# Front_PowerConnectors.net
KiCad netlist of a schematic drawn in Altium Designer
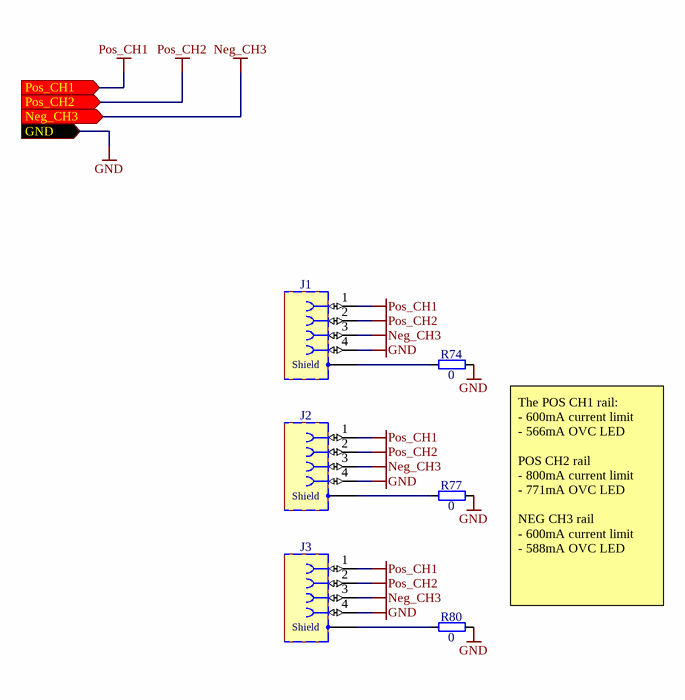
[diagram p0: Front_PowerConnectors.SchDoc]

(export (version "E")
  (design (tool "Eeschema 10.0.6"))
  (components
    (comp (ref "J1")
      (value "M8")
      (footprint "AMPHENOL_M8AS-04PFFR-SF8001")
      (description "Connector 4 Female + Shield")
      (fields
        (field (name "PART NUMBER") "AMPHENOL_M8AS-04PFFR-SF8001")
        (field (name "MANUFACTURER") "AMPHENOL")
        (field (name "AUTHOR") "CERN DEM MR")
      )
      (libsource (lib "Connectors") (part "Connector 4 Female + Shield"))
    )
    (comp (ref "J2")
      (value "M8")
      (footprint "AMPHENOL_M8AS-04PFFR-SF8001")
      (description "Connector 4 Female + Shield")
      (fields
        (field (name "PART NUMBER") "AMPHENOL_M8AS-04PFFR-SF8001")
        (field (name "MANUFACTURER") "AMPHENOL")
        (field (name "AUTHOR") "CERN DEM MR")
      )
      (libsource (lib "Connectors") (part "Connector 4 Female + Shield"))
    )
    (comp (ref "J3")
      (value "M8")
      (footprint "AMPHENOL_M8AS-04PFFR-SF8001")
      (description "Connector 4 Female + Shield")
      (fields
        (field (name "PART NUMBER") "AMPHENOL_M8AS-04PFFR-SF8001")
        (field (name "MANUFACTURER") "AMPHENOL")
        (field (name "AUTHOR") "CERN DEM MR")
      )
      (libsource (lib "Connectors") (part "Connector 4 Female + Shield"))
    )
    (comp (ref "R74")
      (value "0")
      (footprint "RESC1608X55N")
      (description "Resistor")
      (fields
        (field (name "PART NUMBER") "R0603_0R_JUMPER")
        (field (name "MANUFACTURER") "GENERIC")
        (field (name "AUTHOR") "CERN DEM JLC")
      )
      (libsource (lib "Resistors") (part "Resistor"))
    )
    (comp (ref "R77")
      (value "0")
      (footprint "RESC1608X55N")
      (description "Resistor")
      (fields
        (field (name "PART NUMBER") "R0603_0R_JUMPER")
        (field (name "MANUFACTURER") "GENERIC")
        (field (name "AUTHOR") "CERN DEM JLC")
      )
      (libsource (lib "Resistors") (part "Resistor"))
    )
    (comp (ref "R80")
      (value "0")
      (footprint "RESC1608X55N")
      (description "Resistor")
      (fields
        (field (name "PART NUMBER") "R0603_0R_JUMPER")
        (field (name "MANUFACTURER") "GENERIC")
        (field (name "AUTHOR") "CERN DEM JLC")
      )
      (libsource (lib "Resistors") (part "Resistor"))
    )
  )
  (nets
    (net (code "1") (name "GND") (class "Default")
      (node (ref "J1") (pin "4") (pinfunction "4_4") (pintype "bidirectional"))
      (node (ref "J2") (pin "4") (pinfunction "4_4") (pintype "bidirectional"))
      (node (ref "J3") (pin "4") (pinfunction "4_4") (pintype "bidirectional"))
      (node (ref "R74") (pin "1") (pinfunction "1_1") (pintype "passive"))
      (node (ref "R77") (pin "1") (pinfunction "1_1") (pintype "passive"))
      (node (ref "R80") (pin "1") (pinfunction "1_1") (pintype "passive"))
    )
    (net (code "2") (name "Neg_CH3") (class "Default")
      (node (ref "J1") (pin "3") (pinfunction "3_3") (pintype "bidirectional"))
      (node (ref "J2") (pin "3") (pinfunction "3_3") (pintype "bidirectional"))
      (node (ref "J3") (pin "3") (pinfunction "3_3") (pintype "bidirectional"))
    )
    (net (code "3") (name "Net-(J1-PadSHIELD)") (class "Default")
      (node (ref "J1") (pin "SHIELD") (pinfunction "SHIELD_SHIELD") (pintype "passive"))
      (node (ref "R74") (pin "2") (pinfunction "2_2") (pintype "passive"))
    )
    (net (code "4") (name "Net-(J2-PadSHIELD)") (class "Default")
      (node (ref "J2") (pin "SHIELD") (pinfunction "SHIELD_SHIELD") (pintype "passive"))
      (node (ref "R77") (pin "2") (pinfunction "2_2") (pintype "passive"))
    )
    (net (code "5") (name "Net-(J3-PadSHIELD)") (class "Default")
      (node (ref "J3") (pin "SHIELD") (pinfunction "SHIELD_SHIELD") (pintype "passive"))
      (node (ref "R80") (pin "2") (pinfunction "2_2") (pintype "passive"))
    )
    (net (code "6") (name "Pos_CH1") (class "Default")
      (node (ref "J1") (pin "1") (pinfunction "1_1") (pintype "bidirectional"))
      (node (ref "J2") (pin "1") (pinfunction "1_1") (pintype "bidirectional"))
      (node (ref "J3") (pin "1") (pinfunction "1_1") (pintype "bidirectional"))
    )
    (net (code "7") (name "Pos_CH2") (class "Default")
      (node (ref "J1") (pin "2") (pinfunction "2_2") (pintype "bidirectional"))
      (node (ref "J2") (pin "2") (pinfunction "2_2") (pintype "bidirectional"))
      (node (ref "J3") (pin "2") (pinfunction "2_2") (pintype "bidirectional"))
    )
  )
)
